# SRAM_Expansion_Port.net
KiCad netlist of a schematic drawn in Altium Designer
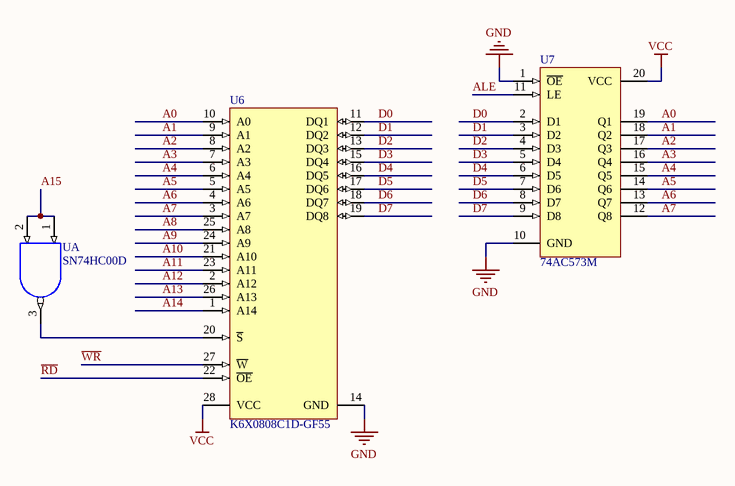
[diagram p0: SRAM & Expansion Port.SchDoc]

(export (version "E")
  (design (tool "Eeschema 10.0.6"))
  (components
    (comp (ref "U")
      (value "SN74HC00D")
      (footprint "D014_N")
      (description "Quadruple 2-Input Positive-NAND Gate")
      (fields (field (name "PUBLISHER") "Altium Limited"))
      (libsource (lib "TI Logic Gate 2") (part "SN74HC00D"))
    )
    (comp (ref "U6")
      (value "K6X0808C1D-GF55")
      (footprint "PRSP0028DB-B_N")
      (description "262144-bit (32768-word x 8-bit) CMOS SRAM")
      (fields (field (name "PUBLISHER") "Altium Limited"))
      (libsource (lib "Renesas Memory") (part "M5M5256DFP-55LL"))
    )
    (comp (ref "U7")
      (value "74AC573M")
      (footprint "SO20_N")
      (description "Octal D-Type Latch with 3-State Output Non-Inverting")
      (fields (field (name "PUBLISHER") "Altium Limited"))
      (libsource (lib "ST Logic Latch") (part "74AC573M"))
    )
  )
  (nets
    (net (code "1") (name "/A0") (class "Default")
      (node (ref "U6") (pin "10") (pinfunction "A0_10") (pintype "input"))
      (node (ref "U7") (pin "19") (pinfunction "Q1_19") (pintype "tri_state"))
    )
    (net (code "2") (name "/A1") (class "Default")
      (node (ref "U6") (pin "9") (pinfunction "A1_9") (pintype "input"))
      (node (ref "U7") (pin "18") (pinfunction "Q2_18") (pintype "tri_state"))
    )
    (net (code "3") (name "/A2") (class "Default")
      (node (ref "U6") (pin "8") (pinfunction "A2_8") (pintype "input"))
      (node (ref "U7") (pin "17") (pinfunction "Q3_17") (pintype "tri_state"))
    )
    (net (code "4") (name "/A3") (class "Default")
      (node (ref "U6") (pin "7") (pinfunction "A3_7") (pintype "input"))
      (node (ref "U7") (pin "16") (pinfunction "Q4_16") (pintype "tri_state"))
    )
    (net (code "5") (name "/A4") (class "Default")
      (node (ref "U6") (pin "6") (pinfunction "A4_6") (pintype "input"))
      (node (ref "U7") (pin "15") (pinfunction "Q5_15") (pintype "tri_state"))
    )
    (net (code "6") (name "/A5") (class "Default")
      (node (ref "U6") (pin "5") (pinfunction "A5_5") (pintype "input"))
      (node (ref "U7") (pin "14") (pinfunction "Q6_14") (pintype "tri_state"))
    )
    (net (code "7") (name "/A6") (class "Default")
      (node (ref "U6") (pin "4") (pinfunction "A6_4") (pintype "input"))
      (node (ref "U7") (pin "13") (pinfunction "Q7_13") (pintype "tri_state"))
    )
    (net (code "8") (name "/A7") (class "Default")
      (node (ref "U6") (pin "3") (pinfunction "A7_3") (pintype "input"))
      (node (ref "U7") (pin "12") (pinfunction "Q8_12") (pintype "tri_state"))
    )
    (net (code "9") (name "/A8") (class "Default")
      (node (ref "U6") (pin "25") (pinfunction "A8_25") (pintype "input"))
    )
    (net (code "10") (name "/A9") (class "Default")
      (node (ref "U6") (pin "24") (pinfunction "A9_24") (pintype "input"))
    )
    (net (code "11") (name "/A10") (class "Default")
      (node (ref "U6") (pin "21") (pinfunction "A10_21") (pintype "input"))
    )
    (net (code "12") (name "/A11") (class "Default")
      (node (ref "U6") (pin "23") (pinfunction "A11_23") (pintype "input"))
    )
    (net (code "13") (name "/A12") (class "Default")
      (node (ref "U6") (pin "2") (pinfunction "A12_2") (pintype "input"))
    )
    (net (code "14") (name "/A13") (class "Default")
      (node (ref "U6") (pin "26") (pinfunction "A13_26") (pintype "input"))
    )
    (net (code "15") (name "/A14") (class "Default")
      (node (ref "U6") (pin "1") (pinfunction "A14_1") (pintype "input"))
    )
    (net (code "16") (name "/A15") (class "Default")
      (node (ref "U") (pin "1") (pinfunction "A_1") (pintype "input"))
      (node (ref "U") (pin "2") (pinfunction "B_2") (pintype "input"))
    )
    (net (code "17") (name "/ALE") (class "Default")
      (node (ref "U7") (pin "11") (pinfunction "LE_11") (pintype "input"))
    )
    (net (code "18") (name "/D0") (class "Default")
      (node (ref "U6") (pin "11") (pinfunction "DQ1_11") (pintype "bidirectional"))
      (node (ref "U7") (pin "2") (pinfunction "D1_2") (pintype "input"))
    )
    (net (code "19") (name "/D1") (class "Default")
      (node (ref "U6") (pin "12") (pinfunction "DQ2_12") (pintype "bidirectional"))
      (node (ref "U7") (pin "3") (pinfunction "D2_3") (pintype "input"))
    )
    (net (code "20") (name "/D2") (class "Default")
      (node (ref "U6") (pin "13") (pinfunction "DQ3_13") (pintype "bidirectional"))
      (node (ref "U7") (pin "4") (pinfunction "D3_4") (pintype "input"))
    )
    (net (code "21") (name "/D3") (class "Default")
      (node (ref "U6") (pin "15") (pinfunction "DQ4_15") (pintype "bidirectional"))
      (node (ref "U7") (pin "5") (pinfunction "D4_5") (pintype "input"))
    )
    (net (code "22") (name "/D4") (class "Default")
      (node (ref "U6") (pin "16") (pinfunction "DQ5_16") (pintype "bidirectional"))
      (node (ref "U7") (pin "6") (pinfunction "D5_6") (pintype "input"))
    )
    (net (code "23") (name "/D5") (class "Default")
      (node (ref "U6") (pin "17") (pinfunction "DQ6_17") (pintype "bidirectional"))
      (node (ref "U7") (pin "7") (pinfunction "D6_7") (pintype "input"))
    )
    (net (code "24") (name "/D6") (class "Default")
      (node (ref "U6") (pin "18") (pinfunction "DQ7_18") (pintype "bidirectional"))
      (node (ref "U7") (pin "8") (pinfunction "D7_8") (pintype "input"))
    )
    (net (code "25") (name "/D7") (class "Default")
      (node (ref "U6") (pin "19") (pinfunction "DQ8_19") (pintype "bidirectional"))
      (node (ref "U7") (pin "9") (pinfunction "D8_9") (pintype "input"))
    )
    (net (code "26") (name "/~{RD}") (class "Default")
      (node (ref "U6") (pin "22") (pinfunction "~{OE}_22") (pintype "input"))
    )
    (net (code "27") (name "/~{WR}") (class "Default")
      (node (ref "U6") (pin "27") (pinfunction "~{W}_27") (pintype "input"))
    )
    (net (code "28") (name "GND") (class "Default")
      (node (ref "U") (pin "7") (pinfunction "GND_7") (pintype "power_in"))
      (node (ref "U6") (pin "14") (pinfunction "GND_14") (pintype "power_in"))
      (node (ref "U7") (pin "1") (pinfunction "~{OE}_1") (pintype "input"))
      (node (ref "U7") (pin "10") (pinfunction "GND_10") (pintype "power_in"))
    )
    (net (code "29") (name "Net-(U6-~{S})") (class "Default")
      (node (ref "U") (pin "3") (pinfunction "Y_3") (pintype "output"))
      (node (ref "U6") (pin "20") (pinfunction "~{S}_20") (pintype "input"))
    )
    (net (code "30") (name "VCC") (class "Default")
      (node (ref "U") (pin "14") (pinfunction "VCC_14") (pintype "power_in"))
      (node (ref "U6") (pin "28") (pinfunction "VCC_28") (pintype "power_in"))
      (node (ref "U7") (pin "20") (pinfunction "VCC_20") (pintype "power_in"))
    )
  )
)
